# l1-logo_profiled.net
KiCad netlist of a schematic drawn in EAGLE
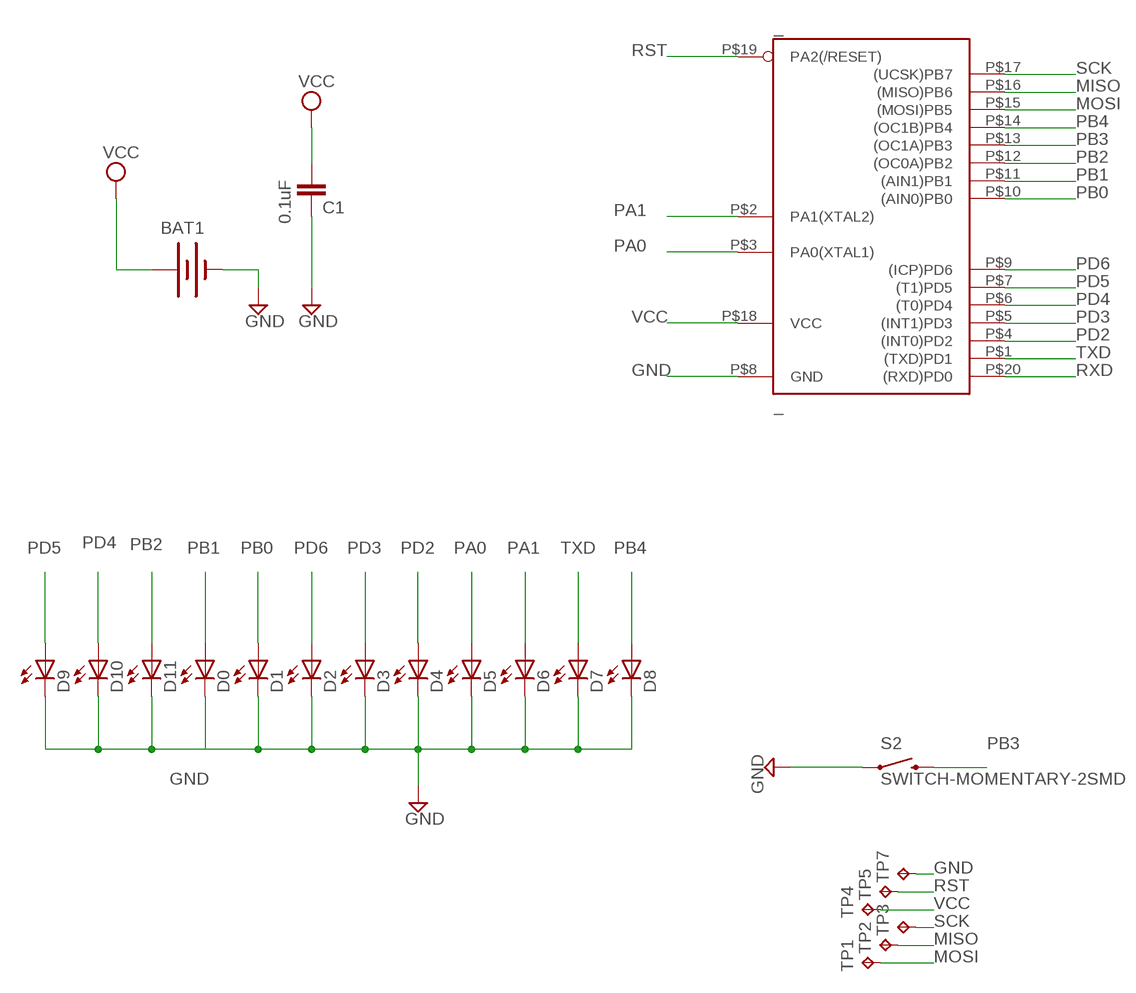
[diagram p0: schematic, sheet 1]

(export (version "E")
  (design (tool "Eeschema 10.0.6"))
  (components
    (comp (ref "BAT1")
      (value "SPARKFUN_BATTERYSPARKFUN_BATTCOMM_20MM_LINX")
      (footprint "eagle-import:SPARKFUN_BATTCOM_20MM_LINX")
      (libsource (lib "eagle-import") (part "SPARKFUN_BATTERYSPARKFUN_BATTCOMM_20MM_LINX"))
    )
    (comp (ref "C1")
      (value "0.1uF")
      (footprint "eagle-import:0805")
      (libsource (lib "eagle-import") (part "CAP0805"))
    )
    (comp (ref "D0")
      (value "SPARKFUN_LED1206")
      (footprint "eagle-import:SPARKFUN_LED-1206")
      (libsource (lib "eagle-import") (part "SPARKFUN_LED1206"))
    )
    (comp (ref "D1")
      (value "SPARKFUN_LED1206")
      (footprint "eagle-import:SPARKFUN_LED-1206")
      (libsource (lib "eagle-import") (part "SPARKFUN_LED1206"))
    )
    (comp (ref "D2")
      (value "SPARKFUN_LED1206")
      (footprint "eagle-import:SPARKFUN_LED-1206")
      (libsource (lib "eagle-import") (part "SPARKFUN_LED1206"))
    )
    (comp (ref "D3")
      (value "SPARKFUN_LED1206")
      (footprint "eagle-import:SPARKFUN_LED-1206")
      (libsource (lib "eagle-import") (part "SPARKFUN_LED1206"))
    )
    (comp (ref "D4")
      (value "SPARKFUN_LED1206")
      (footprint "eagle-import:SPARKFUN_LED-1206")
      (libsource (lib "eagle-import") (part "SPARKFUN_LED1206"))
    )
    (comp (ref "D5")
      (value "SPARKFUN_LED1206")
      (footprint "eagle-import:SPARKFUN_LED-1206")
      (libsource (lib "eagle-import") (part "SPARKFUN_LED1206"))
    )
    (comp (ref "D6")
      (value "SPARKFUN_LED1206")
      (footprint "eagle-import:SPARKFUN_LED-1206")
      (libsource (lib "eagle-import") (part "SPARKFUN_LED1206"))
    )
    (comp (ref "D7")
      (value "SPARKFUN_LED1206")
      (footprint "eagle-import:SPARKFUN_LED-1206")
      (libsource (lib "eagle-import") (part "SPARKFUN_LED1206"))
    )
    (comp (ref "D8")
      (value "SPARKFUN_LED1206")
      (footprint "eagle-import:SPARKFUN_LED-1206")
      (libsource (lib "eagle-import") (part "SPARKFUN_LED1206"))
    )
    (comp (ref "D9")
      (value "SPARKFUN_LED1206")
      (footprint "eagle-import:SPARKFUN_LED-1206")
      (libsource (lib "eagle-import") (part "SPARKFUN_LED1206"))
    )
    (comp (ref "D10")
      (value "SPARKFUN_LED1206")
      (footprint "eagle-import:SPARKFUN_LED-1206")
      (libsource (lib "eagle-import") (part "SPARKFUN_LED1206"))
    )
    (comp (ref "D11")
      (value "SPARKFUN_LED1206")
      (footprint "eagle-import:SPARKFUN_LED-1206")
      (libsource (lib "eagle-import") (part "SPARKFUN_LED1206"))
    )
    (comp (ref "S2")
      (value "SWITCH-MOMENTARY-2SMD")
      (footprint "eagle-import:TACTILE_SWITCH_SMD")
      (libsource (lib "eagle-import") (part "SWITCH-MOMENTARY-2SMD"))
    )
    (comp (ref "TP1")
      (value "TPTP18R")
      (footprint "eagle-import:TP18R")
      (libsource (lib "eagle-import") (part "TPTP18R"))
    )
    (comp (ref "TP2")
      (value "TPTP18R")
      (footprint "eagle-import:TP18R")
      (libsource (lib "eagle-import") (part "TPTP18R"))
    )
    (comp (ref "TP3")
      (value "TPTP18R")
      (footprint "eagle-import:TP18R")
      (libsource (lib "eagle-import") (part "TPTP18R"))
    )
    (comp (ref "TP4")
      (value "TPTP18R")
      (footprint "eagle-import:TP18R")
      (libsource (lib "eagle-import") (part "TPTP18R"))
    )
    (comp (ref "TP5")
      (value "TPTP18R")
      (footprint "eagle-import:TP18R")
      (libsource (lib "eagle-import") (part "TPTP18R"))
    )
    (comp (ref "TP7")
      (value "TPTP18R")
      (footprint "eagle-import:TP18R")
      (libsource (lib "eagle-import") (part "TPTP18R"))
    )
    (comp (ref "_")
      (value "_")
      (footprint "eagle-import:MLF20")
      (libsource (lib "eagle-import") (part "TINY2313-M"))
    )
  )
  (nets
    (net (code "1") (name "/MISO") (class "Default")
      (node (ref "TP2") (pin "TP") (pinfunction "TP_TP") (pintype "input"))
      (node (ref "_") (pin "P$16") (pinfunction "(MISO)PB6_P$16") (pintype "bidirectional"))
    )
    (net (code "2") (name "/MOSI") (class "Default")
      (node (ref "TP1") (pin "TP") (pinfunction "TP_TP") (pintype "input"))
      (node (ref "_") (pin "P$15") (pinfunction "(MOSI)PB5_P$15") (pintype "bidirectional"))
    )
    (net (code "3") (name "/PA0") (class "Default")
      (node (ref "D5") (pin "A") (pinfunction "A_A") (pintype "passive"))
      (node (ref "_") (pin "P$3") (pinfunction "PA0(XTAL1)_P$3") (pintype "bidirectional"))
    )
    (net (code "4") (name "/PA1") (class "Default")
      (node (ref "D6") (pin "A") (pinfunction "A_A") (pintype "passive"))
      (node (ref "_") (pin "P$2") (pinfunction "PA1(XTAL2)_P$2") (pintype "bidirectional"))
    )
    (net (code "5") (name "/PB0") (class "Default")
      (node (ref "D1") (pin "A") (pinfunction "A_A") (pintype "passive"))
      (node (ref "_") (pin "P$10") (pinfunction "(AIN0)PB0_P$10") (pintype "bidirectional"))
    )
    (net (code "6") (name "/PB1") (class "Default")
      (node (ref "D0") (pin "A") (pinfunction "A_A") (pintype "passive"))
      (node (ref "_") (pin "P$11") (pinfunction "(AIN1)PB1_P$11") (pintype "bidirectional"))
    )
    (net (code "7") (name "/PB2") (class "Default")
      (node (ref "D11") (pin "A") (pinfunction "A_A") (pintype "passive"))
      (node (ref "_") (pin "P$12") (pinfunction "(OC0A)PB2_P$12") (pintype "bidirectional"))
    )
    (net (code "8") (name "/PB3") (class "Default")
      (node (ref "S2") (pin "3") (pinfunction "2_3") (pintype "passive"))
      (node (ref "_") (pin "P$13") (pinfunction "(OC1A)PB3_P$13") (pintype "bidirectional"))
    )
    (net (code "9") (name "/PB4") (class "Default")
      (node (ref "D8") (pin "A") (pinfunction "A_A") (pintype "passive"))
      (node (ref "_") (pin "P$14") (pinfunction "(OC1B)PB4_P$14") (pintype "bidirectional"))
    )
    (net (code "10") (name "/PD2") (class "Default")
      (node (ref "D4") (pin "A") (pinfunction "A_A") (pintype "passive"))
      (node (ref "_") (pin "P$4") (pinfunction "(INT0)PD2_P$4") (pintype "bidirectional"))
    )
    (net (code "11") (name "/PD3") (class "Default")
      (node (ref "D3") (pin "A") (pinfunction "A_A") (pintype "passive"))
      (node (ref "_") (pin "P$5") (pinfunction "(INT1)PD3_P$5") (pintype "bidirectional"))
    )
    (net (code "12") (name "/PD4") (class "Default")
      (node (ref "D10") (pin "A") (pinfunction "A_A") (pintype "passive"))
      (node (ref "_") (pin "P$6") (pinfunction "(T0)PD4_P$6") (pintype "bidirectional"))
    )
    (net (code "13") (name "/PD5") (class "Default")
      (node (ref "D9") (pin "A") (pinfunction "A_A") (pintype "passive"))
      (node (ref "_") (pin "P$7") (pinfunction "(T1)PD5_P$7") (pintype "bidirectional"))
    )
    (net (code "14") (name "/PD6") (class "Default")
      (node (ref "D2") (pin "A") (pinfunction "A_A") (pintype "passive"))
      (node (ref "_") (pin "P$9") (pinfunction "(ICP)PD6_P$9") (pintype "bidirectional"))
    )
    (net (code "15") (name "/RST") (class "Default")
      (node (ref "TP5") (pin "TP") (pinfunction "TP_TP") (pintype "input"))
      (node (ref "_") (pin "P$19") (pinfunction "PA2(/RESET)_P$19") (pintype "input"))
    )
    (net (code "16") (name "/RXD") (class "Default")
      (node (ref "_") (pin "P$20") (pinfunction "(RXD)PD0_P$20") (pintype "bidirectional"))
    )
    (net (code "17") (name "/SCK") (class "Default")
      (node (ref "TP3") (pin "TP") (pinfunction "TP_TP") (pintype "input"))
      (node (ref "_") (pin "P$17") (pinfunction "(UCSK)PB7_P$17") (pintype "bidirectional"))
    )
    (net (code "18") (name "/TXD") (class "Default")
      (node (ref "D7") (pin "A") (pinfunction "A_A") (pintype "passive"))
      (node (ref "_") (pin "P$1") (pinfunction "(TXD)PD1_P$1") (pintype "bidirectional"))
    )
    (net (code "19") (name "GND") (class "Default")
      (node (ref "BAT1") (pin "2") (pinfunction "-_2") (pintype "power_in"))
      (node (ref "C1") (pin "2") (pinfunction "2_2") (pintype "passive"))
      (node (ref "D0") (pin "C") (pinfunction "C_C") (pintype "passive"))
      (node (ref "D1") (pin "C") (pinfunction "C_C") (pintype "passive"))
      (node (ref "D10") (pin "C") (pinfunction "C_C") (pintype "passive"))
      (node (ref "D11") (pin "C") (pinfunction "C_C") (pintype "passive"))
      (node (ref "D2") (pin "C") (pinfunction "C_C") (pintype "passive"))
      (node (ref "D3") (pin "C") (pinfunction "C_C") (pintype "passive"))
      (node (ref "D4") (pin "C") (pinfunction "C_C") (pintype "passive"))
      (node (ref "D5") (pin "C") (pinfunction "C_C") (pintype "passive"))
      (node (ref "D6") (pin "C") (pinfunction "C_C") (pintype "passive"))
      (node (ref "D7") (pin "C") (pinfunction "C_C") (pintype "passive"))
      (node (ref "D8") (pin "C") (pinfunction "C_C") (pintype "passive"))
      (node (ref "D9") (pin "C") (pinfunction "C_C") (pintype "passive"))
      (node (ref "S2") (pin "1") (pinfunction "1_1") (pintype "passive"))
      (node (ref "TP7") (pin "TP") (pinfunction "TP_TP") (pintype "input"))
      (node (ref "_") (pin "P$8") (pinfunction "GND_P$8") (pintype "power_in"))
    )
    (net (code "20") (name "VCC") (class "Default")
      (node (ref "BAT1") (pin "1") (pinfunction "+_1") (pintype "power_in"))
      (node (ref "C1") (pin "1") (pinfunction "1_1") (pintype "passive"))
      (node (ref "TP4") (pin "TP") (pinfunction "TP_TP") (pintype "input"))
      (node (ref "_") (pin "P$18") (pinfunction "VCC_P$18") (pintype "power_in"))
    )
  )
)
